# WX0_011_324DL.net
KiCad netlist of a schematic drawn in Altium Designer
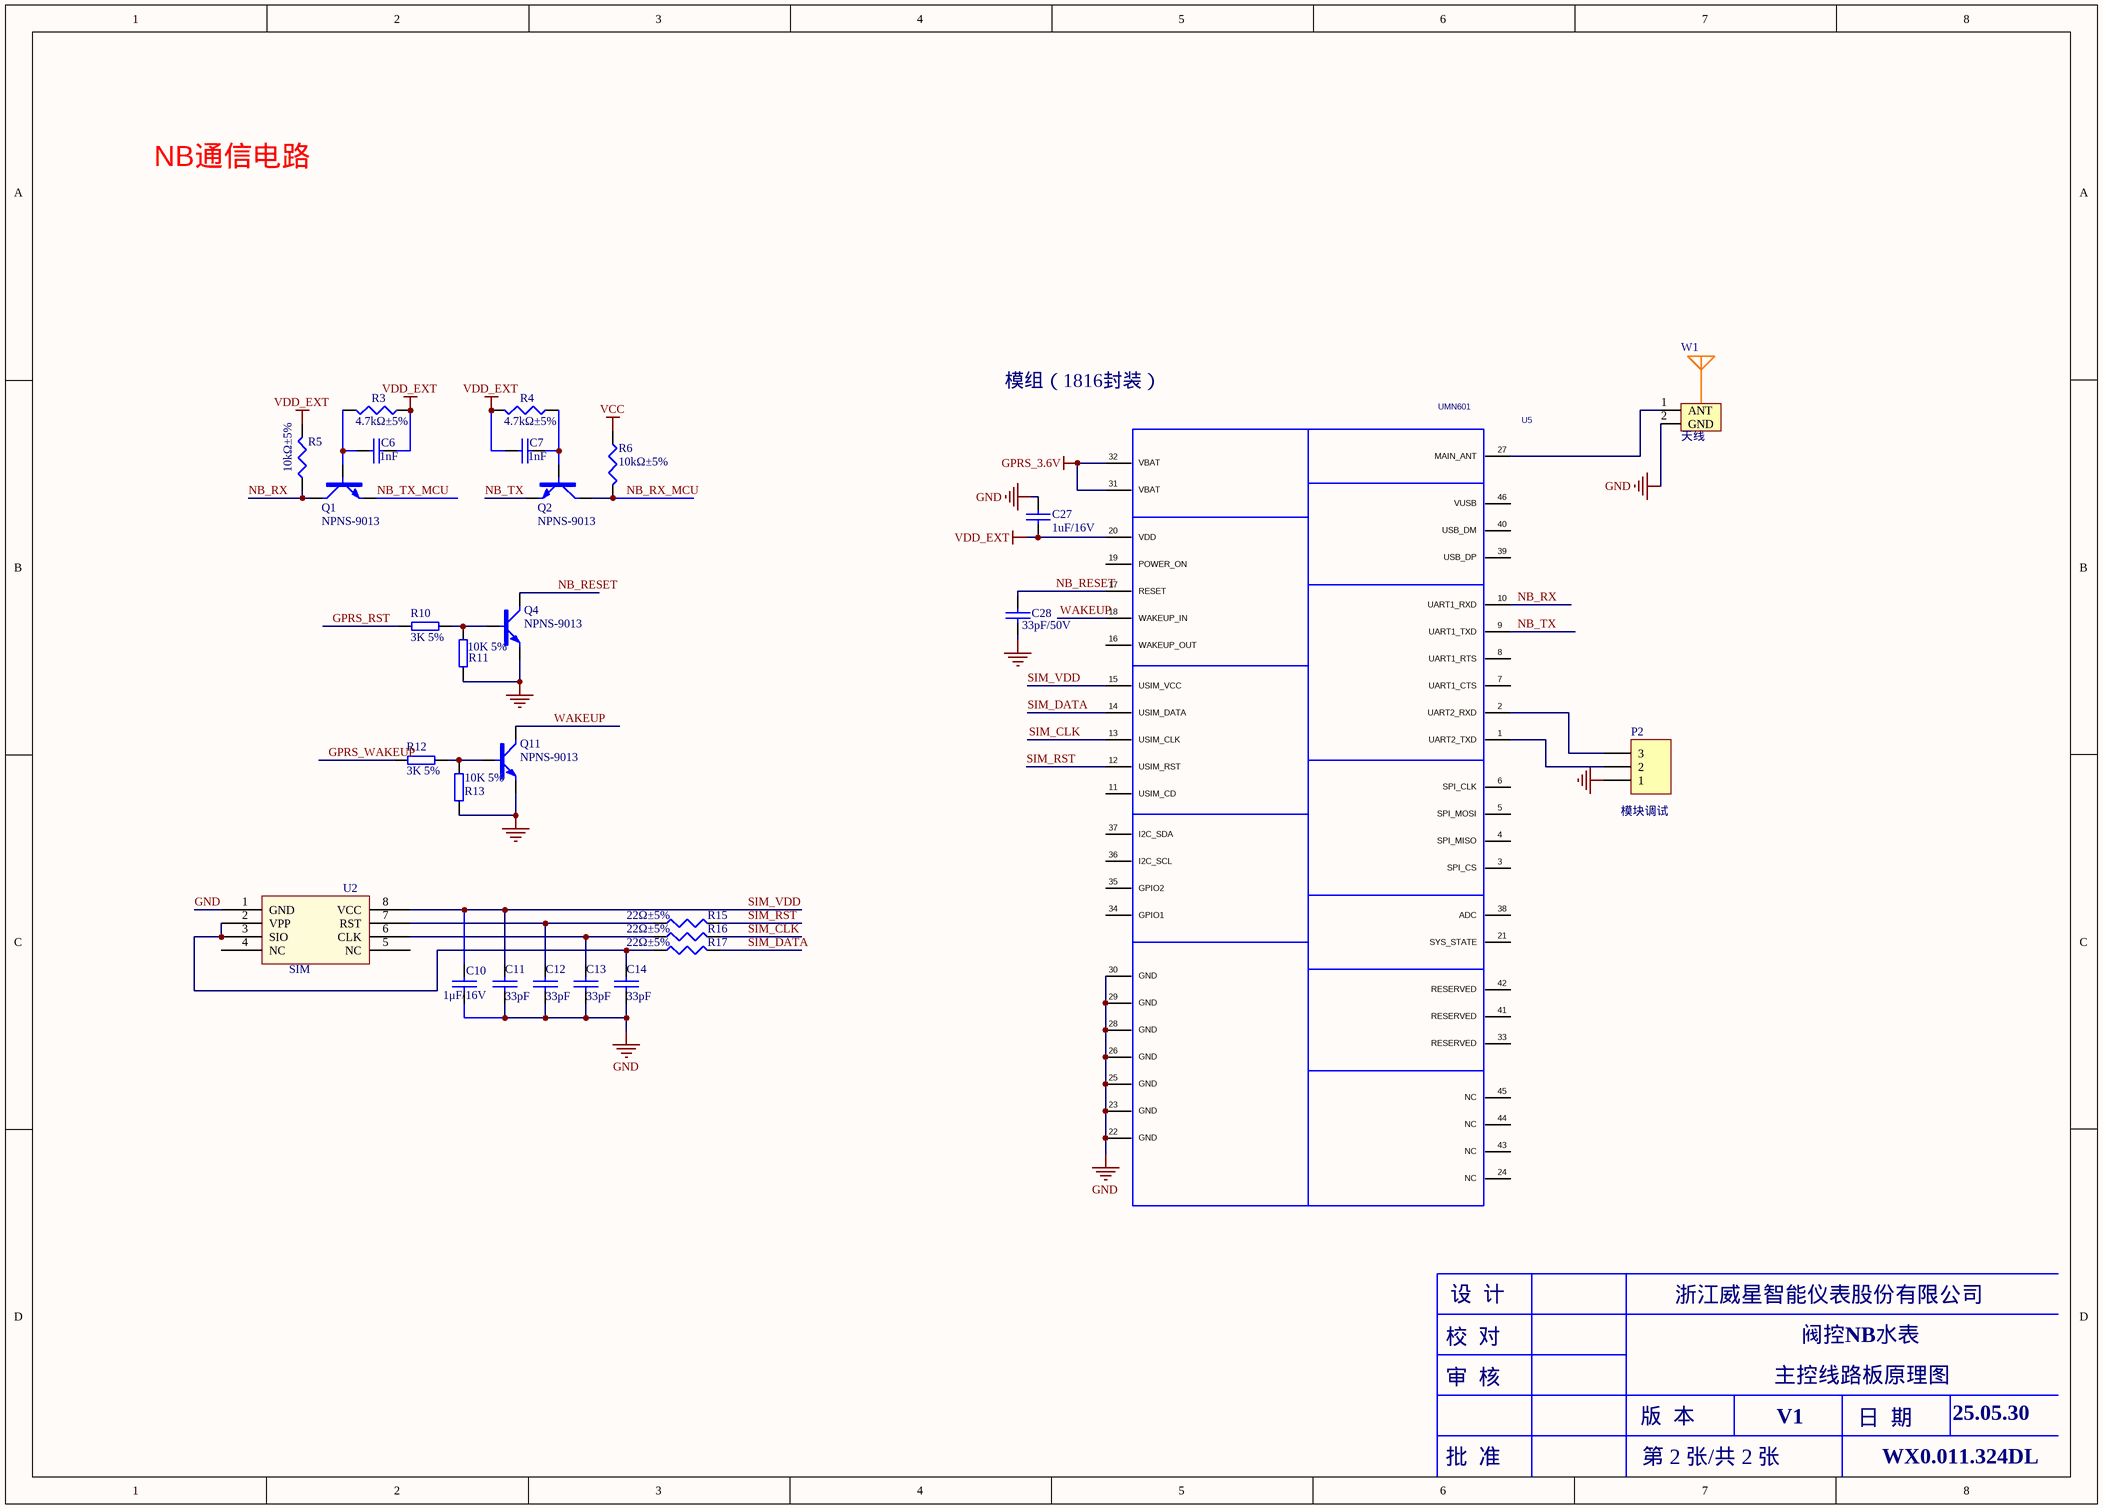
[diagram p0: WX0.011.324DL.SchDoc]

(export (version "E")
  (design (tool "Eeschema 10.0.6"))
  (components
    (comp (ref "C6")
      (value "1nF")
      (footprint "CAP0603")
      (description "贴片电容,1nF±10%/50V,X7R,国巨")
      (fields (field (name "PART NUMBER") "101020103-0022") (field (name "MANUFACTURER") "国巨"))
      (libsource (lib "Devices") (part "CAP"))
    )
    (comp (ref "C7")
      (value "1nF")
      (footprint "CAP0603")
      (description "贴片电容,1nF±10%/50V,X7R,国巨")
      (fields (field (name "PART NUMBER") "101020103-0022") (field (name "MANUFACTURER") "国巨"))
      (libsource (lib "Devices") (part "CAP"))
    )
    (comp (ref "C10")
      (value "1μF/16V")
      (footprint "CAP0603")
      (description "贴片电容,1μF±10%/16V,X7R,国巨")
      (fields (field (name "PART NUMBER") "101020103-0003") (field (name "MANUFACTURER") "国巨"))
      (libsource (lib "Devices") (part "CAP"))
    )
    (comp (ref "C11")
      (value "33pF")
      (footprint "CAP0603")
      (description "贴片电容,33pF±10%/50V,NP0,国巨")
      (fields (field (name "PART NUMBER") "101020103-0027") (field (name "MANUFACTURER") "国巨"))
      (libsource (lib "Devices") (part "CAP"))
    )
    (comp (ref "C12")
      (value "33pF")
      (footprint "CAP0603")
      (description "贴片电容,33pF±10%/50V,NP0,国巨")
      (fields (field (name "PART NUMBER") "101020103-0027") (field (name "MANUFACTURER") "国巨"))
      (libsource (lib "Devices") (part "CAP"))
    )
    (comp (ref "C13")
      (value "33pF")
      (footprint "CAP0603")
      (description "贴片电容,33pF±10%/50V,NP0,国巨")
      (fields (field (name "PART NUMBER") "101020103-0027") (field (name "MANUFACTURER") "国巨"))
      (libsource (lib "Devices") (part "CAP"))
    )
    (comp (ref "C14")
      (value "33pF")
      (footprint "CAP0603")
      (description "贴片电容,33pF±10%/50V,NP0,国巨")
      (fields (field (name "PART NUMBER") "101020103-0027") (field (name "MANUFACTURER") "国巨"))
      (libsource (lib "Devices") (part "CAP"))
    )
    (comp (ref "C27")
      (value "1uF/16V")
      (footprint "CAP0603")
      (description "105pF,16 V,±10%,0603,国巨,CC0603KRX7R7BB105")
      (fields (field (name "PART NUMBER") "101020103-0003"))
      (libsource (lib "Database_Libs1") (part "CC03K7R7_1U"))
    )
    (comp (ref "C28")
      (value "33pF/50V")
      (footprint "CAP0603")
      (description "33pF,50 V,±10%,0603,国巨,CC0603KRNPO9BN33")
      (fields (field (name "PART NUMBER") "101020103-0027"))
      (libsource (lib "Database_Libs2") (part "CC03KPO9_33P"))
    )
    (comp (ref "P2")
      (value "模块调试")
      (footprint "PIN254_1*3*WXHJ")
      (description "1*3 ，Φ1.0 ，2.54mm，直脚,无需焊接器件")
      (fields (field (name "PART NUMBER") "AD_WXHJ_PinHeader_04"))
      (libsource (lib "Database_Libs2") (part "PIN254_1*3*WXHJ"))
    )
    (comp (ref "Q1")
      (value "NPNS-9013")
      (footprint "SOT-23")
      (description "9013,NPN,SOT-23,长电,S9013")
      (fields (field (name "PART NUMBER") "101040201-0002"))
      (libsource (lib "Database_Libs2") (part "03_NPNS-9013"))
    )
    (comp (ref "Q2")
      (value "NPNS-9013")
      (footprint "SOT-23")
      (description "9013,NPN,SOT-23,长电,S9013")
      (fields (field (name "PART NUMBER") "101040201-0002"))
      (libsource (lib "Database_Libs2") (part "03_NPNS-9013"))
    )
    (comp (ref "Q4")
      (value "NPNS-9013")
      (footprint "SOT-23")
      (description "9013,NPN,SOT-23,长电,S9013")
      (fields (field (name "PART NUMBER") "101040201-0002"))
      (libsource (lib "Database_Libs2") (part "03_NPNS-9013"))
    )
    (comp (ref "Q11")
      (value "NPNS-9013")
      (footprint "SOT-23")
      (description "9013,NPN,SOT-23,长电,S9013")
      (fields (field (name "PART NUMBER") "101040201-0002"))
      (libsource (lib "Database_Libs2") (part "03_NPNS-9013"))
    )
    (comp (ref "R3")
      (value "4.7kΩ±5%")
      (footprint "RES0603")
      (description "贴片电阻,4.7kΩ±5%,1/10W,100ppm/℃,国巨")
      (fields (field (name "PART NUMBER") "101010103-0042") (field (name "MANUFACTURER") "国巨"))
      (libsource (lib "Devices") (part "RES1"))
    )
    (comp (ref "R4")
      (value "4.7kΩ±5%")
      (footprint "RES0603")
      (description "贴片电阻,4.7kΩ±5%,1/10W,100ppm/℃,国巨")
      (fields (field (name "PART NUMBER") "101010103-0042") (field (name "MANUFACTURER") "国巨"))
      (libsource (lib "Devices") (part "RES1"))
    )
    (comp (ref "R5")
      (value "10kΩ±5%")
      (footprint "RES0603")
      (description "贴片电阻,10kΩ±5%,1/10W,100ppm/℃,国巨")
      (fields (field (name "PART NUMBER") "101010103-0003") (field (name "MANUFACTURER") "国巨"))
      (libsource (lib "Devices") (part "RES1"))
    )
    (comp (ref "R6")
      (value "10kΩ±5%")
      (footprint "RES0603")
      (description "贴片电阻,10kΩ±5%,1/10W,100ppm/℃,国巨")
      (fields (field (name "PART NUMBER") "101010103-0003") (field (name "MANUFACTURER") "国巨"))
      (libsource (lib "Devices") (part "RES1"))
    )
    (comp (ref "R10")
      (value "3K 5%")
      (footprint "RES0603")
      (description "国巨,±5%,0603,,155 ℃,-55 ℃,RC0603JR-073KL,无铅,100 ppm/℃,1/10W,,3K")
      (fields (field (name "PART NUMBER") "101010103-0006"))
      (libsource (lib "Database_Libs2") (part "RC03J_3K"))
    )
    (comp (ref "R11")
      (value "10K 5%")
      (footprint "RES0603")
      (description "国巨,±5%,0603,,155 ℃,-55 ℃,RC0603JR-0710KL,无铅,200 ppm/℃,1/10W,,10K")
      (fields (field (name "PART NUMBER") "101010103-0003"))
      (libsource (lib "Database_Libs2") (part "RC03J_10K"))
    )
    (comp (ref "R12")
      (value "3K 5%")
      (footprint "RES0603")
      (description "国巨,±5%,0603,,155 ℃,-55 ℃,RC0603JR-073KL,无铅,100 ppm/℃,1/10W,,3K")
      (fields (field (name "PART NUMBER") "101010103-0006"))
      (libsource (lib "Database_Libs2") (part "RC03J_3K"))
    )
    (comp (ref "R13")
      (value "10K 5%")
      (footprint "RES0603")
      (description "国巨,±5%,0603,,155 ℃,-55 ℃,RC0603JR-0710KL,无铅,200 ppm/℃,1/10W,,10K")
      (fields (field (name "PART NUMBER") "101010103-0003"))
      (libsource (lib "Database_Libs2") (part "RC03J_10K"))
    )
    (comp (ref "R15")
      (value "22Ω±5%")
      (footprint "RES0603")
      (description "贴片电阻,22Ω±5%,1/10W,100ppm/℃,国巨")
      (fields (field (name "PART NUMBER") "101010103-0009") (field (name "MANUFACTURER") "国巨"))
      (libsource (lib "Devices") (part "RES1"))
    )
    (comp (ref "R16")
      (value "22Ω±5%")
      (footprint "RES0603")
      (description "贴片电阻,22Ω±5%,1/10W,100ppm/℃,国巨")
      (fields (field (name "PART NUMBER") "101010103-0009") (field (name "MANUFACTURER") "国巨"))
      (libsource (lib "Database_Libs2") (part "RES1"))
    )
    (comp (ref "R17")
      (value "22Ω±5%")
      (footprint "RES0603")
      (description "贴片电阻,22Ω±5%,1/10W,100ppm/℃,国巨")
      (fields (field (name "PART NUMBER") "101010103-0009") (field (name "MANUFACTURER") "国巨"))
      (libsource (lib "Devices") (part "RES1"))
    )
    (comp (ref "U2")
      (value "SIM")
      (footprint "SIMIC")
      (description "集成电路,ESIM,杭州电信")
      (fields (field (name "PART NUMBER") "101050101-0120") (field (name "MANUFACTURER") "电信"))
      (libsource (lib "Devices") (part "ESIM"))
    )
    (comp (ref "U5")
      (value "UMN601")
      (footprint "N700-FIXTURE_DL_CFT_CQA")
      (description "N700-58-01,N700-58-01,通信模块,18.0mm*16.0mm*2.1mm,Band 5:850MHz/Band 8:900MHz,深圳市广和通无线股份有限公司")
      (fields (field (name "PART NUMBER") "1011402-0183"))
      (libsource (lib "Database_Libs2") (part "01_N700_CON_46"))
    )
    (comp (ref "W1")
      (value "天线")
      (footprint "ANT-tanpian")
      (description "UB06000058A,3*3.1*1.25mm,公头,单排,IPEX一代板端")
      (fields (field (name "PART NUMBER") "1010902-0145"))
      (libsource (lib "Database_Libs2") (part "天线"))
    )
  )
  (nets
    (net (code "1") (name "/GPRS_RST") (class "Default")
      (node (ref "R10") (pin "1") (pinfunction "1_1") (pintype "passive"))
    )
    (net (code "2") (name "/GPRS_WAKEUP") (class "Default")
      (node (ref "R12") (pin "1") (pinfunction "1_1") (pintype "passive"))
    )
    (net (code "3") (name "/NB_RESET") (class "Default")
      (node (ref "C28") (pin "2") (pinfunction "2_2") (pintype "passive"))
      (node (ref "Q4") (pin "3") (pinfunction "C_3") (pintype "passive"))
      (node (ref "U5") (pin "17") (pinfunction "RESET_17") (pintype "passive"))
    )
    (net (code "4") (name "/NB_RX") (class "Default")
      (node (ref "Q1") (pin "3") (pinfunction "C_3") (pintype "passive"))
      (node (ref "R5") (pin "1") (pinfunction "1_1") (pintype "passive"))
      (node (ref "U5") (pin "10") (pinfunction "UART1_RXD_10") (pintype "passive"))
    )
    (net (code "5") (name "/NB_RX_MCU") (class "Default")
      (node (ref "Q2") (pin "3") (pinfunction "C_3") (pintype "passive"))
      (node (ref "R6") (pin "2") (pinfunction "2_2") (pintype "passive"))
    )
    (net (code "6") (name "/NB_TX") (class "Default")
      (node (ref "Q2") (pin "2") (pinfunction "E_2") (pintype "passive"))
      (node (ref "U5") (pin "9") (pinfunction "UART1_TXD_9") (pintype "passive"))
    )
    (net (code "7") (name "/NB_TX_MCU") (class "Default")
      (node (ref "Q1") (pin "2") (pinfunction "E_2") (pintype "passive"))
    )
    (net (code "8") (name "/SIM_CLK") (class "Default")
      (node (ref "R16") (pin "2") (pinfunction "2_2") (pintype "passive"))
      (node (ref "U5") (pin "13") (pinfunction "USIM_CLK_13") (pintype "passive"))
    )
    (net (code "9") (name "/SIM_DATA") (class "Default")
      (node (ref "R17") (pin "2") (pinfunction "2_2") (pintype "passive"))
      (node (ref "U5") (pin "14") (pinfunction "USIM_DATA_14") (pintype "passive"))
    )
    (net (code "10") (name "/SIM_RST") (class "Default")
      (node (ref "R15") (pin "2") (pinfunction "2_2") (pintype "passive"))
      (node (ref "U5") (pin "12") (pinfunction "USIM_RST_12") (pintype "passive"))
    )
    (net (code "11") (name "/SIM_VDD") (class "Default")
      (node (ref "C10") (pin "2") (pinfunction "2_2") (pintype "passive"))
      (node (ref "C11") (pin "2") (pinfunction "2_2") (pintype "passive"))
      (node (ref "U2") (pin "8") (pinfunction "VCC_8") (pintype "passive"))
      (node (ref "U5") (pin "15") (pinfunction "USIM_VCC_15") (pintype "passive"))
    )
    (net (code "12") (name "/WAKEUP") (class "Default")
      (node (ref "Q11") (pin "3") (pinfunction "C_3") (pintype "passive"))
      (node (ref "U5") (pin "18") (pinfunction "WAKEUP_IN_18") (pintype "passive"))
    )
    (net (code "13") (name "GND") (class "Default")
      (node (ref "C10") (pin "1") (pinfunction "1_1") (pintype "passive"))
      (node (ref "C11") (pin "1") (pinfunction "1_1") (pintype "passive"))
      (node (ref "C12") (pin "1") (pinfunction "1_1") (pintype "passive"))
      (node (ref "C13") (pin "1") (pinfunction "1_1") (pintype "passive"))
      (node (ref "C14") (pin "1") (pinfunction "1_1") (pintype "passive"))
      (node (ref "C27") (pin "2") (pinfunction "2_2") (pintype "passive"))
      (node (ref "C28") (pin "1") (pinfunction "1_1") (pintype "passive"))
      (node (ref "P2") (pin "1") (pinfunction "1_1") (pintype "passive"))
      (node (ref "Q11") (pin "2") (pinfunction "E_2") (pintype "passive"))
      (node (ref "Q4") (pin "2") (pinfunction "E_2") (pintype "passive"))
      (node (ref "R11") (pin "1") (pinfunction "1_1") (pintype "passive"))
      (node (ref "R13") (pin "1") (pinfunction "1_1") (pintype "passive"))
      (node (ref "U2") (pin "1") (pinfunction "GND_1") (pintype "passive"))
      (node (ref "U5") (pin "22") (pinfunction "GND_22") (pintype "passive"))
      (node (ref "U5") (pin "23") (pinfunction "GND_23") (pintype "passive"))
      (node (ref "U5") (pin "25") (pinfunction "GND_25") (pintype "passive"))
      (node (ref "U5") (pin "26") (pinfunction "GND_26") (pintype "passive"))
      (node (ref "U5") (pin "28") (pinfunction "GND_28") (pintype "passive"))
      (node (ref "U5") (pin "29") (pinfunction "GND_29") (pintype "passive"))
      (node (ref "U5") (pin "30") (pinfunction "GND_30") (pintype "passive"))
      (node (ref "W1") (pin "2") (pinfunction "GND_2") (pintype "passive"))
    )
    (net (code "14") (name "GPRS_3.6V") (class "Default")
      (node (ref "U5") (pin "31") (pinfunction "VBAT_31") (pintype "passive"))
      (node (ref "U5") (pin "32") (pinfunction "VBAT_32") (pintype "passive"))
    )
    (net (code "15") (name "Net-(Q1-B)") (class "Default")
      (node (ref "C6") (pin "1") (pinfunction "1_1") (pintype "passive"))
      (node (ref "Q1") (pin "1") (pinfunction "B_1") (pintype "passive"))
      (node (ref "R3") (pin "2") (pinfunction "2_2") (pintype "passive"))
    )
    (net (code "16") (name "Net-(Q2-B)") (class "Default")
      (node (ref "C7") (pin "2") (pinfunction "2_2") (pintype "passive"))
      (node (ref "Q2") (pin "1") (pinfunction "B_1") (pintype "passive"))
      (node (ref "R4") (pin "1") (pinfunction "1_1") (pintype "passive"))
    )
    (net (code "17") (name "Net-(Q4-B)") (class "Default")
      (node (ref "Q4") (pin "1") (pinfunction "B_1") (pintype "passive"))
      (node (ref "R10") (pin "2") (pinfunction "2_2") (pintype "passive"))
      (node (ref "R11") (pin "2") (pinfunction "2_2") (pintype "passive"))
    )
    (net (code "18") (name "Net-(Q11-B)") (class "Default")
      (node (ref "Q11") (pin "1") (pinfunction "B_1") (pintype "passive"))
      (node (ref "R12") (pin "2") (pinfunction "2_2") (pintype "passive"))
      (node (ref "R13") (pin "2") (pinfunction "2_2") (pintype "passive"))
    )
    (net (code "19") (name "Net-(U2-CLK)") (class "Default")
      (node (ref "C13") (pin "2") (pinfunction "2_2") (pintype "passive"))
      (node (ref "R16") (pin "1") (pinfunction "1_1") (pintype "passive"))
      (node (ref "U2") (pin "6") (pinfunction "CLK_6") (pintype "passive"))
    )
    (net (code "20") (name "Net-(U2-RST)") (class "Default")
      (node (ref "C12") (pin "2") (pinfunction "2_2") (pintype "passive"))
      (node (ref "R15") (pin "1") (pinfunction "1_1") (pintype "passive"))
      (node (ref "U2") (pin "7") (pinfunction "RST_7") (pintype "passive"))
    )
    (net (code "21") (name "Net-(U2-SIO)") (class "Default")
      (node (ref "C14") (pin "2") (pinfunction "2_2") (pintype "passive"))
      (node (ref "R17") (pin "1") (pinfunction "1_1") (pintype "passive"))
      (node (ref "U2") (pin "2") (pinfunction "VPP_2") (pintype "passive"))
      (node (ref "U2") (pin "3") (pinfunction "SIO_3") (pintype "passive"))
    )
    (net (code "22") (name "Net-(U5-MAIN_ANT)") (class "Default")
      (node (ref "U5") (pin "27") (pinfunction "MAIN_ANT_27") (pintype "passive"))
      (node (ref "W1") (pin "1") (pinfunction "ANT_1") (pintype "passive"))
    )
    (net (code "23") (name "Net-(U5-UART2_RXD)") (class "Default")
      (node (ref "P2") (pin "3") (pinfunction "3_3") (pintype "passive"))
      (node (ref "U5") (pin "2") (pinfunction "UART2_RXD_2") (pintype "passive"))
    )
    (net (code "24") (name "Net-(U5-UART2_TXD)") (class "Default")
      (node (ref "P2") (pin "2") (pinfunction "2_2") (pintype "passive"))
      (node (ref "U5") (pin "1") (pinfunction "UART2_TXD_1") (pintype "passive"))
    )
    (net (code "25") (name "VCC") (class "Default")
      (node (ref "R6") (pin "1") (pinfunction "1_1") (pintype "passive"))
    )
    (net (code "26") (name "VDD_EXT") (class "Default")
      (node (ref "C27") (pin "1") (pinfunction "1_1") (pintype "passive"))
      (node (ref "C6") (pin "2") (pinfunction "2_2") (pintype "passive"))
      (node (ref "C7") (pin "1") (pinfunction "1_1") (pintype "passive"))
      (node (ref "R3") (pin "1") (pinfunction "1_1") (pintype "passive"))
      (node (ref "R4") (pin "2") (pinfunction "2_2") (pintype "passive"))
      (node (ref "R5") (pin "2") (pinfunction "2_2") (pintype "passive"))
      (node (ref "U5") (pin "20") (pinfunction "VDD_20") (pintype "passive"))
    )
    (net (code "27") (name "unconnected-(U2-NC-Pad4)") (class "Default")
      (node (ref "U2") (pin "4") (pinfunction "NC_4") (pintype "passive"))
    )
    (net (code "28") (name "unconnected-(U2-NC-Pad5)") (class "Default")
      (node (ref "U2") (pin "5") (pinfunction "NC_5") (pintype "passive"))
    )
    (net (code "29") (name "unconnected-(U5-ADC-Pad38)") (class "Default")
      (node (ref "U5") (pin "38") (pinfunction "ADC_38") (pintype "passive"))
    )
    (net (code "30") (name "unconnected-(U5-GPIO1-Pad34)") (class "Default")
      (node (ref "U5") (pin "34") (pinfunction "GPIO1_34") (pintype "passive"))
    )
    (net (code "31") (name "unconnected-(U5-GPIO2-Pad35)") (class "Default")
      (node (ref "U5") (pin "35") (pinfunction "GPIO2_35") (pintype "passive"))
    )
    (net (code "32") (name "unconnected-(U5-I2C_SCL-Pad36)") (class "Default")
      (node (ref "U5") (pin "36") (pinfunction "I2C_SCL_36") (pintype "passive"))
    )
    (net (code "33") (name "unconnected-(U5-I2C_SDA-Pad37)") (class "Default")
      (node (ref "U5") (pin "37") (pinfunction "I2C_SDA_37") (pintype "passive"))
    )
    (net (code "34") (name "unconnected-(U5-NC-Pad24)") (class "Default")
      (node (ref "U5") (pin "24") (pinfunction "NC_24") (pintype "passive"))
    )
    (net (code "35") (name "unconnected-(U5-NC-Pad43)") (class "Default")
      (node (ref "U5") (pin "43") (pinfunction "NC_43") (pintype "passive"))
    )
    (net (code "36") (name "unconnected-(U5-NC-Pad44)") (class "Default")
      (node (ref "U5") (pin "44") (pinfunction "NC_44") (pintype "passive"))
    )
    (net (code "37") (name "unconnected-(U5-NC-Pad45)") (class "Default")
      (node (ref "U5") (pin "45") (pinfunction "NC_45") (pintype "passive"))
    )
    (net (code "38") (name "unconnected-(U5-POWER_ON-Pad19)") (class "Default")
      (node (ref "U5") (pin "19") (pinfunction "POWER_ON_19") (pintype "passive"))
    )
    (net (code "39") (name "unconnected-(U5-RESERVED-Pad33)") (class "Default")
      (node (ref "U5") (pin "33") (pinfunction "RESERVED_33") (pintype "passive"))
    )
    (net (code "40") (name "unconnected-(U5-RESERVED-Pad41)") (class "Default")
      (node (ref "U5") (pin "41") (pinfunction "RESERVED_41") (pintype "passive"))
    )
    (net (code "41") (name "unconnected-(U5-RESERVED-Pad42)") (class "Default")
      (node (ref "U5") (pin "42") (pinfunction "RESERVED_42") (pintype "passive"))
    )
    (net (code "42") (name "unconnected-(U5-SPI_CLK-Pad6)") (class "Default")
      (node (ref "U5") (pin "6") (pinfunction "SPI_CLK_6") (pintype "passive"))
    )
    (net (code "43") (name "unconnected-(U5-SPI_CS-Pad3)") (class "Default")
      (node (ref "U5") (pin "3") (pinfunction "SPI_CS_3") (pintype "passive"))
    )
    (net (code "44") (name "unconnected-(U5-SPI_MISO-Pad4)") (class "Default")
      (node (ref "U5") (pin "4") (pinfunction "SPI_MISO_4") (pintype "passive"))
    )
    (net (code "45") (name "unconnected-(U5-SPI_MOSI-Pad5)") (class "Default")
      (node (ref "U5") (pin "5") (pinfunction "SPI_MOSI_5") (pintype "passive"))
    )
    (net (code "46") (name "unconnected-(U5-SYS_STATE-Pad21)") (class "Default")
      (node (ref "U5") (pin "21") (pinfunction "SYS_STATE_21") (pintype "passive"))
    )
    (net (code "47") (name "unconnected-(U5-UART1_CTS-Pad7)") (class "Default")
      (node (ref "U5") (pin "7") (pinfunction "UART1_CTS_7") (pintype "passive"))
    )
    (net (code "48") (name "unconnected-(U5-UART1_RTS-Pad8)") (class "Default")
      (node (ref "U5") (pin "8") (pinfunction "UART1_RTS_8") (pintype "passive"))
    )
    (net (code "49") (name "unconnected-(U5-USB_DM-Pad40)") (class "Default")
      (node (ref "U5") (pin "40") (pinfunction "USB_DM_40") (pintype "passive"))
    )
    (net (code "50") (name "unconnected-(U5-USB_DP-Pad39)") (class "Default")
      (node (ref "U5") (pin "39") (pinfunction "USB_DP_39") (pintype "passive"))
    )
    (net (code "51") (name "unconnected-(U5-USIM_CD-Pad11)") (class "Default")
      (node (ref "U5") (pin "11") (pinfunction "USIM_CD_11") (pintype "passive"))
    )
    (net (code "52") (name "unconnected-(U5-VUSB-Pad46)") (class "Default")
      (node (ref "U5") (pin "46") (pinfunction "VUSB_46") (pintype "passive"))
    )
    (net (code "53") (name "unconnected-(U5-WAKEUP_OUT-Pad16)") (class "Default")
      (node (ref "U5") (pin "16") (pinfunction "WAKEUP_OUT_16") (pintype "passive"))
    )
  )
)
